# interloper-v1.net
KiCad netlist of a schematic drawn in EAGLE
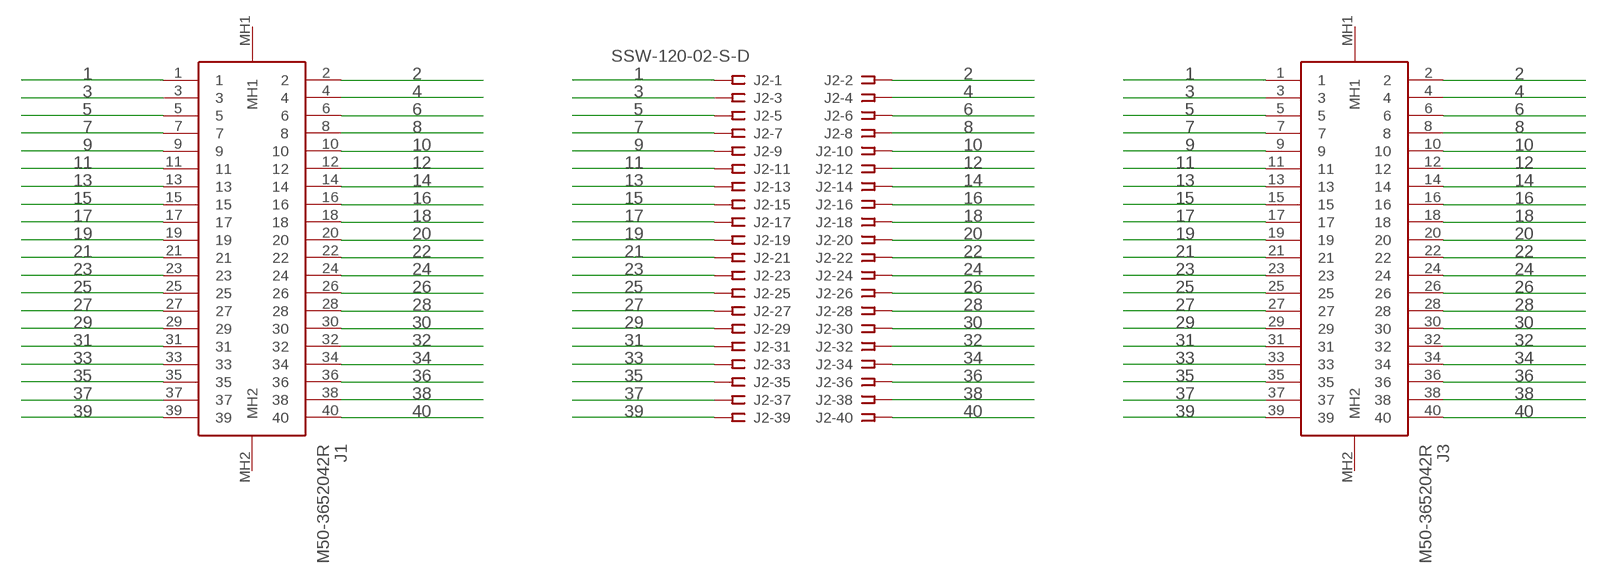
[diagram p0: schematic, sheet 1]

(export (version "E")
  (design (tool "Eeschema 10.0.6"))
  (components
    (comp (ref "J1")
      (value "M50-3652042R")
      (footprint "eagle-import:M503652042R")
      (fields (field (name "MOUSER_PART_NUMBER") "855-M50-3652042R"))
      (libsource (lib "eagle-import") (part "M50-3652042R"))
    )
    (comp (ref "J2")
      (value "SSW-120-02-S-D")
      (footprint "eagle-import:SSW-120-02-S-D")
      (libsource (lib "eagle-import") (part "SSW-120-02-S-D"))
    )
    (comp (ref "J3")
      (value "M50-3652042R")
      (footprint "eagle-import:M503652042R")
      (fields (field (name "MOUSER_PART_NUMBER") "855-M50-3652042R"))
      (libsource (lib "eagle-import") (part "M50-3652042R"))
    )
  )
  (nets
    (net (code "1") (name "/1") (class "Default")
      (node (ref "J1") (pin "1") (pinfunction "1_1") (pintype "bidirectional"))
      (node (ref "J2") (pin "1") (pinfunction "1_1") (pintype "passive"))
      (node (ref "J3") (pin "1") (pinfunction "1_1") (pintype "bidirectional"))
    )
    (net (code "2") (name "/2") (class "Default")
      (node (ref "J1") (pin "2") (pinfunction "2_2") (pintype "bidirectional"))
      (node (ref "J2") (pin "2") (pinfunction "1_2") (pintype "passive"))
      (node (ref "J3") (pin "2") (pinfunction "2_2") (pintype "bidirectional"))
    )
    (net (code "3") (name "/3") (class "Default")
      (node (ref "J1") (pin "3") (pinfunction "3_3") (pintype "bidirectional"))
      (node (ref "J2") (pin "3") (pinfunction "1_3") (pintype "passive"))
      (node (ref "J3") (pin "3") (pinfunction "3_3") (pintype "bidirectional"))
    )
    (net (code "4") (name "/4") (class "Default")
      (node (ref "J1") (pin "4") (pinfunction "4_4") (pintype "bidirectional"))
      (node (ref "J2") (pin "4") (pinfunction "1_4") (pintype "passive"))
      (node (ref "J3") (pin "4") (pinfunction "4_4") (pintype "bidirectional"))
    )
    (net (code "5") (name "/5") (class "Default")
      (node (ref "J1") (pin "5") (pinfunction "5_5") (pintype "bidirectional"))
      (node (ref "J2") (pin "5") (pinfunction "1_5") (pintype "passive"))
      (node (ref "J3") (pin "5") (pinfunction "5_5") (pintype "bidirectional"))
    )
    (net (code "6") (name "/6") (class "Default")
      (node (ref "J1") (pin "6") (pinfunction "6_6") (pintype "bidirectional"))
      (node (ref "J2") (pin "6") (pinfunction "1_6") (pintype "passive"))
      (node (ref "J3") (pin "6") (pinfunction "6_6") (pintype "bidirectional"))
    )
    (net (code "7") (name "/7") (class "Default")
      (node (ref "J1") (pin "7") (pinfunction "7_7") (pintype "bidirectional"))
      (node (ref "J2") (pin "7") (pinfunction "1_7") (pintype "passive"))
      (node (ref "J3") (pin "7") (pinfunction "7_7") (pintype "bidirectional"))
    )
    (net (code "8") (name "/8") (class "Default")
      (node (ref "J1") (pin "8") (pinfunction "8_8") (pintype "bidirectional"))
      (node (ref "J2") (pin "8") (pinfunction "1_8") (pintype "passive"))
      (node (ref "J3") (pin "8") (pinfunction "8_8") (pintype "bidirectional"))
    )
    (net (code "9") (name "/9") (class "Default")
      (node (ref "J1") (pin "9") (pinfunction "9_9") (pintype "bidirectional"))
      (node (ref "J2") (pin "9") (pinfunction "1_9") (pintype "passive"))
      (node (ref "J3") (pin "9") (pinfunction "9_9") (pintype "bidirectional"))
    )
    (net (code "10") (name "/10") (class "Default")
      (node (ref "J1") (pin "10") (pinfunction "10_10") (pintype "bidirectional"))
      (node (ref "J2") (pin "10") (pinfunction "1_10") (pintype "passive"))
      (node (ref "J3") (pin "10") (pinfunction "10_10") (pintype "bidirectional"))
    )
    (net (code "11") (name "/11") (class "Default")
      (node (ref "J1") (pin "11") (pinfunction "11_11") (pintype "bidirectional"))
      (node (ref "J2") (pin "11") (pinfunction "1_11") (pintype "passive"))
      (node (ref "J3") (pin "11") (pinfunction "11_11") (pintype "bidirectional"))
    )
    (net (code "12") (name "/12") (class "Default")
      (node (ref "J1") (pin "12") (pinfunction "12_12") (pintype "bidirectional"))
      (node (ref "J2") (pin "12") (pinfunction "1_12") (pintype "passive"))
      (node (ref "J3") (pin "12") (pinfunction "12_12") (pintype "bidirectional"))
    )
    (net (code "13") (name "/13") (class "Default")
      (node (ref "J1") (pin "13") (pinfunction "13_13") (pintype "bidirectional"))
      (node (ref "J2") (pin "13") (pinfunction "1_13") (pintype "passive"))
      (node (ref "J3") (pin "13") (pinfunction "13_13") (pintype "bidirectional"))
    )
    (net (code "14") (name "/14") (class "Default")
      (node (ref "J1") (pin "14") (pinfunction "14_14") (pintype "bidirectional"))
      (node (ref "J2") (pin "14") (pinfunction "1_14") (pintype "passive"))
      (node (ref "J3") (pin "14") (pinfunction "14_14") (pintype "bidirectional"))
    )
    (net (code "15") (name "/15") (class "Default")
      (node (ref "J1") (pin "15") (pinfunction "15_15") (pintype "bidirectional"))
      (node (ref "J2") (pin "15") (pinfunction "1_15") (pintype "passive"))
      (node (ref "J3") (pin "15") (pinfunction "15_15") (pintype "bidirectional"))
    )
    (net (code "16") (name "/16") (class "Default")
      (node (ref "J1") (pin "16") (pinfunction "16_16") (pintype "bidirectional"))
      (node (ref "J2") (pin "16") (pinfunction "1_16") (pintype "passive"))
      (node (ref "J3") (pin "16") (pinfunction "16_16") (pintype "bidirectional"))
    )
    (net (code "17") (name "/17") (class "Default")
      (node (ref "J1") (pin "17") (pinfunction "17_17") (pintype "bidirectional"))
      (node (ref "J2") (pin "17") (pinfunction "1_17") (pintype "passive"))
      (node (ref "J3") (pin "17") (pinfunction "17_17") (pintype "bidirectional"))
    )
    (net (code "18") (name "/18") (class "Default")
      (node (ref "J1") (pin "18") (pinfunction "18_18") (pintype "bidirectional"))
      (node (ref "J2") (pin "18") (pinfunction "1_18") (pintype "passive"))
      (node (ref "J3") (pin "18") (pinfunction "18_18") (pintype "bidirectional"))
    )
    (net (code "19") (name "/19") (class "Default")
      (node (ref "J1") (pin "19") (pinfunction "19_19") (pintype "bidirectional"))
      (node (ref "J2") (pin "19") (pinfunction "1_19") (pintype "passive"))
      (node (ref "J3") (pin "19") (pinfunction "19_19") (pintype "bidirectional"))
    )
    (net (code "20") (name "/20") (class "Default")
      (node (ref "J1") (pin "20") (pinfunction "20_20") (pintype "bidirectional"))
      (node (ref "J2") (pin "20") (pinfunction "1_20") (pintype "passive"))
      (node (ref "J3") (pin "20") (pinfunction "20_20") (pintype "bidirectional"))
    )
    (net (code "21") (name "/21") (class "Default")
      (node (ref "J1") (pin "21") (pinfunction "21_21") (pintype "bidirectional"))
      (node (ref "J2") (pin "21") (pinfunction "1_21") (pintype "passive"))
      (node (ref "J3") (pin "21") (pinfunction "21_21") (pintype "bidirectional"))
    )
    (net (code "22") (name "/22") (class "Default")
      (node (ref "J1") (pin "22") (pinfunction "22_22") (pintype "bidirectional"))
      (node (ref "J2") (pin "22") (pinfunction "1_22") (pintype "passive"))
      (node (ref "J3") (pin "22") (pinfunction "22_22") (pintype "bidirectional"))
    )
    (net (code "23") (name "/23") (class "Default")
      (node (ref "J1") (pin "23") (pinfunction "23_23") (pintype "bidirectional"))
      (node (ref "J2") (pin "23") (pinfunction "1_23") (pintype "passive"))
      (node (ref "J3") (pin "23") (pinfunction "23_23") (pintype "bidirectional"))
    )
    (net (code "24") (name "/24") (class "Default")
      (node (ref "J1") (pin "24") (pinfunction "24_24") (pintype "bidirectional"))
      (node (ref "J2") (pin "24") (pinfunction "1_24") (pintype "passive"))
      (node (ref "J3") (pin "24") (pinfunction "24_24") (pintype "bidirectional"))
    )
    (net (code "25") (name "/25") (class "Default")
      (node (ref "J1") (pin "25") (pinfunction "25_25") (pintype "bidirectional"))
      (node (ref "J2") (pin "25") (pinfunction "1_25") (pintype "passive"))
      (node (ref "J3") (pin "25") (pinfunction "25_25") (pintype "bidirectional"))
    )
    (net (code "26") (name "/26") (class "Default")
      (node (ref "J1") (pin "26") (pinfunction "26_26") (pintype "bidirectional"))
      (node (ref "J2") (pin "26") (pinfunction "1_26") (pintype "passive"))
      (node (ref "J3") (pin "26") (pinfunction "26_26") (pintype "bidirectional"))
    )
    (net (code "27") (name "/27") (class "Default")
      (node (ref "J1") (pin "27") (pinfunction "27_27") (pintype "bidirectional"))
      (node (ref "J2") (pin "27") (pinfunction "1_27") (pintype "passive"))
      (node (ref "J3") (pin "27") (pinfunction "27_27") (pintype "bidirectional"))
    )
    (net (code "28") (name "/28") (class "Default")
      (node (ref "J1") (pin "28") (pinfunction "28_28") (pintype "bidirectional"))
      (node (ref "J2") (pin "28") (pinfunction "1_28") (pintype "passive"))
      (node (ref "J3") (pin "28") (pinfunction "28_28") (pintype "bidirectional"))
    )
    (net (code "29") (name "/29") (class "Default")
      (node (ref "J1") (pin "29") (pinfunction "29_29") (pintype "bidirectional"))
      (node (ref "J2") (pin "29") (pinfunction "1_29") (pintype "passive"))
      (node (ref "J3") (pin "29") (pinfunction "29_29") (pintype "bidirectional"))
    )
    (net (code "30") (name "/30") (class "Default")
      (node (ref "J1") (pin "30") (pinfunction "30_30") (pintype "bidirectional"))
      (node (ref "J2") (pin "30") (pinfunction "1_30") (pintype "passive"))
      (node (ref "J3") (pin "30") (pinfunction "30_30") (pintype "bidirectional"))
    )
    (net (code "31") (name "/31") (class "Default")
      (node (ref "J1") (pin "31") (pinfunction "31_31") (pintype "bidirectional"))
      (node (ref "J2") (pin "31") (pinfunction "1_31") (pintype "passive"))
      (node (ref "J3") (pin "31") (pinfunction "31_31") (pintype "bidirectional"))
    )
    (net (code "32") (name "/32") (class "Default")
      (node (ref "J1") (pin "32") (pinfunction "32_32") (pintype "bidirectional"))
      (node (ref "J2") (pin "32") (pinfunction "1_32") (pintype "passive"))
      (node (ref "J3") (pin "32") (pinfunction "32_32") (pintype "bidirectional"))
    )
    (net (code "33") (name "/33") (class "Default")
      (node (ref "J1") (pin "33") (pinfunction "33_33") (pintype "bidirectional"))
      (node (ref "J2") (pin "33") (pinfunction "1_33") (pintype "passive"))
      (node (ref "J3") (pin "33") (pinfunction "33_33") (pintype "bidirectional"))
    )
    (net (code "34") (name "/34") (class "Default")
      (node (ref "J1") (pin "34") (pinfunction "34_34") (pintype "bidirectional"))
      (node (ref "J2") (pin "34") (pinfunction "1_34") (pintype "passive"))
      (node (ref "J3") (pin "34") (pinfunction "34_34") (pintype "bidirectional"))
    )
    (net (code "35") (name "/35") (class "Default")
      (node (ref "J1") (pin "35") (pinfunction "35_35") (pintype "bidirectional"))
      (node (ref "J2") (pin "35") (pinfunction "1_35") (pintype "passive"))
      (node (ref "J3") (pin "35") (pinfunction "35_35") (pintype "bidirectional"))
    )
    (net (code "36") (name "/36") (class "Default")
      (node (ref "J1") (pin "36") (pinfunction "36_36") (pintype "bidirectional"))
      (node (ref "J2") (pin "36") (pinfunction "1_36") (pintype "passive"))
      (node (ref "J3") (pin "36") (pinfunction "36_36") (pintype "bidirectional"))
    )
    (net (code "37") (name "/37") (class "Default")
      (node (ref "J1") (pin "37") (pinfunction "37_37") (pintype "bidirectional"))
      (node (ref "J2") (pin "37") (pinfunction "1_37") (pintype "passive"))
      (node (ref "J3") (pin "37") (pinfunction "37_37") (pintype "bidirectional"))
    )
    (net (code "38") (name "/38") (class "Default")
      (node (ref "J1") (pin "38") (pinfunction "38_38") (pintype "bidirectional"))
      (node (ref "J2") (pin "38") (pinfunction "1_38") (pintype "passive"))
      (node (ref "J3") (pin "38") (pinfunction "38_38") (pintype "bidirectional"))
    )
    (net (code "39") (name "/39") (class "Default")
      (node (ref "J1") (pin "39") (pinfunction "39_39") (pintype "bidirectional"))
      (node (ref "J2") (pin "39") (pinfunction "1_39") (pintype "passive"))
      (node (ref "J3") (pin "39") (pinfunction "39_39") (pintype "bidirectional"))
    )
    (net (code "40") (name "/40") (class "Default")
      (node (ref "J1") (pin "40") (pinfunction "40_40") (pintype "bidirectional"))
      (node (ref "J2") (pin "40") (pinfunction "1_40") (pintype "passive"))
      (node (ref "J3") (pin "40") (pinfunction "40_40") (pintype "bidirectional"))
    )
    (net (code "41") (name "unconnected-(J1-PadMH1)") (class "Default")
      (node (ref "J1") (pin "MH1") (pinfunction "MH1_MH1") (pintype "bidirectional"))
    )
    (net (code "42") (name "unconnected-(J1-PadMH2)") (class "Default")
      (node (ref "J1") (pin "MH2") (pinfunction "MH2_MH2") (pintype "bidirectional"))
    )
    (net (code "43") (name "unconnected-(J3-PadMH1)") (class "Default")
      (node (ref "J3") (pin "MH1") (pinfunction "MH1_MH1") (pintype "bidirectional"))
    )
    (net (code "44") (name "unconnected-(J3-PadMH2)") (class "Default")
      (node (ref "J3") (pin "MH2") (pinfunction "MH2_MH2") (pintype "bidirectional"))
    )
  )
)
